# 1-Schematic_SuperCharger_v1.net
KiCad netlist of a schematic drawn in EasyEDA
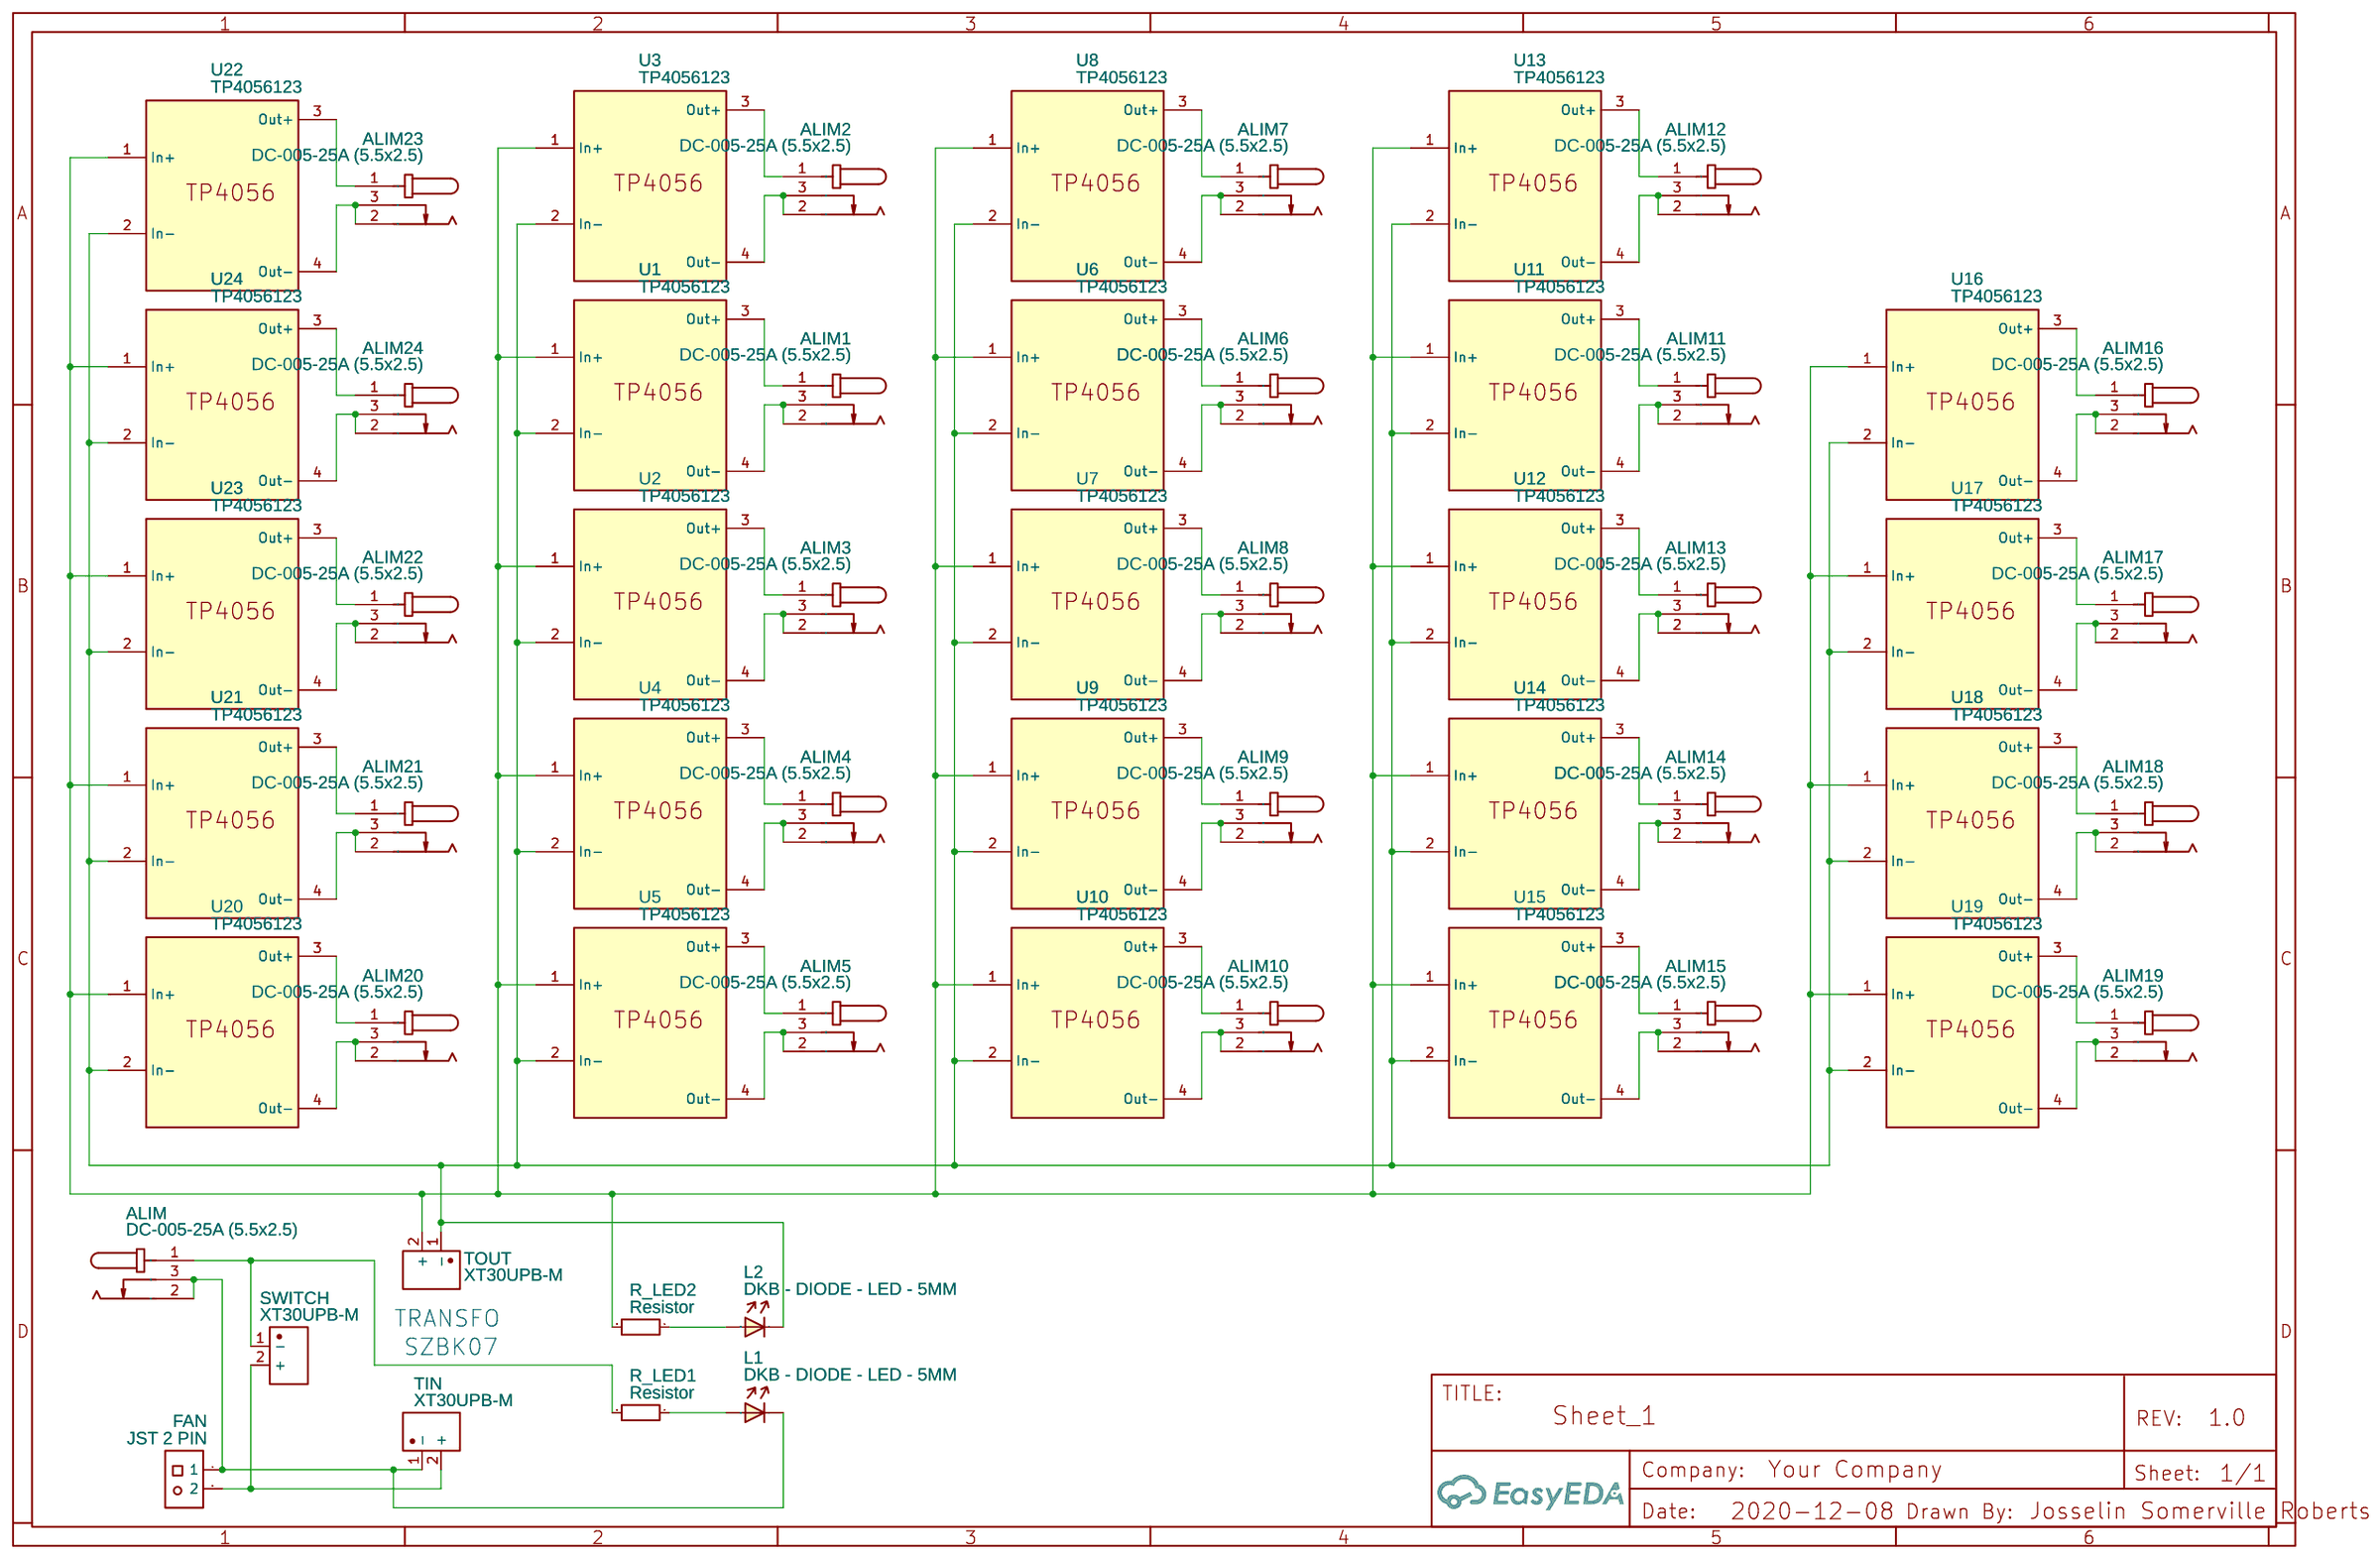
[diagram p0: schematic sheet]

(export (version "E")
  (design (tool "Eeschema 10.0.6"))
  (components
    (comp (ref "ALIM")
      (value "DC-005-25A (5.5x2.5)")
      (fields
        (field (name "BOM_Manufacturer Part") "DC-005-25A")
        (field (name "BOM_Supplier Part") "C136715")
      )
      (libsource (lib "") (part "DC-005-25A (5.5x2.5)_1"))
    )
    (comp (ref "ALIM1")
      (value "DC-005-25A (5.5x2.5)")
      (fields
        (field (name "BOM_Manufacturer Part") "DC-005-25A")
        (field (name "BOM_Supplier Part") "C136715")
      )
      (libsource (lib "") (part "DC-005-25A (5.5x2.5)"))
    )
    (comp (ref "ALIM2")
      (value "DC-005-25A (5.5x2.5)")
      (fields
        (field (name "BOM_Manufacturer Part") "DC-005-25A")
        (field (name "BOM_Supplier Part") "C136715")
      )
      (libsource (lib "") (part "DC-005-25A (5.5x2.5)"))
    )
    (comp (ref "ALIM3")
      (value "DC-005-25A (5.5x2.5)")
      (fields
        (field (name "BOM_Manufacturer Part") "DC-005-25A")
        (field (name "BOM_Supplier Part") "C136715")
      )
      (libsource (lib "") (part "DC-005-25A (5.5x2.5)"))
    )
    (comp (ref "ALIM4")
      (value "DC-005-25A (5.5x2.5)")
      (fields
        (field (name "BOM_Manufacturer Part") "DC-005-25A")
        (field (name "BOM_Supplier Part") "C136715")
      )
      (libsource (lib "") (part "DC-005-25A (5.5x2.5)"))
    )
    (comp (ref "ALIM5")
      (value "DC-005-25A (5.5x2.5)")
      (fields
        (field (name "BOM_Manufacturer Part") "DC-005-25A")
        (field (name "BOM_Supplier Part") "C136715")
      )
      (libsource (lib "") (part "DC-005-25A (5.5x2.5)"))
    )
    (comp (ref "ALIM6")
      (value "DC-005-25A (5.5x2.5)")
      (fields
        (field (name "BOM_Manufacturer Part") "DC-005-25A")
        (field (name "BOM_Supplier Part") "C136715")
      )
      (libsource (lib "") (part "DC-005-25A (5.5x2.5)"))
    )
    (comp (ref "ALIM7")
      (value "DC-005-25A (5.5x2.5)")
      (fields
        (field (name "BOM_Manufacturer Part") "DC-005-25A")
        (field (name "BOM_Supplier Part") "C136715")
      )
      (libsource (lib "") (part "DC-005-25A (5.5x2.5)"))
    )
    (comp (ref "ALIM8")
      (value "DC-005-25A (5.5x2.5)")
      (fields
        (field (name "BOM_Manufacturer Part") "DC-005-25A")
        (field (name "BOM_Supplier Part") "C136715")
      )
      (libsource (lib "") (part "DC-005-25A (5.5x2.5)"))
    )
    (comp (ref "ALIM9")
      (value "DC-005-25A (5.5x2.5)")
      (fields
        (field (name "BOM_Manufacturer Part") "DC-005-25A")
        (field (name "BOM_Supplier Part") "C136715")
      )
      (libsource (lib "") (part "DC-005-25A (5.5x2.5)"))
    )
    (comp (ref "ALIM10")
      (value "DC-005-25A (5.5x2.5)")
      (fields
        (field (name "BOM_Manufacturer Part") "DC-005-25A")
        (field (name "BOM_Supplier Part") "C136715")
      )
      (libsource (lib "") (part "DC-005-25A (5.5x2.5)"))
    )
    (comp (ref "ALIM11")
      (value "DC-005-25A (5.5x2.5)")
      (fields
        (field (name "BOM_Manufacturer Part") "DC-005-25A")
        (field (name "BOM_Supplier Part") "C136715")
      )
      (libsource (lib "") (part "DC-005-25A (5.5x2.5)"))
    )
    (comp (ref "ALIM12")
      (value "DC-005-25A (5.5x2.5)")
      (fields
        (field (name "BOM_Manufacturer Part") "DC-005-25A")
        (field (name "BOM_Supplier Part") "C136715")
      )
      (libsource (lib "") (part "DC-005-25A (5.5x2.5)"))
    )
    (comp (ref "ALIM13")
      (value "DC-005-25A (5.5x2.5)")
      (fields
        (field (name "BOM_Manufacturer Part") "DC-005-25A")
        (field (name "BOM_Supplier Part") "C136715")
      )
      (libsource (lib "") (part "DC-005-25A (5.5x2.5)"))
    )
    (comp (ref "ALIM14")
      (value "DC-005-25A (5.5x2.5)")
      (fields
        (field (name "BOM_Manufacturer Part") "DC-005-25A")
        (field (name "BOM_Supplier Part") "C136715")
      )
      (libsource (lib "") (part "DC-005-25A (5.5x2.5)"))
    )
    (comp (ref "ALIM15")
      (value "DC-005-25A (5.5x2.5)")
      (fields
        (field (name "BOM_Manufacturer Part") "DC-005-25A")
        (field (name "BOM_Supplier Part") "C136715")
      )
      (libsource (lib "") (part "DC-005-25A (5.5x2.5)"))
    )
    (comp (ref "ALIM16")
      (value "DC-005-25A (5.5x2.5)")
      (fields
        (field (name "BOM_Manufacturer Part") "DC-005-25A")
        (field (name "BOM_Supplier Part") "C136715")
      )
      (libsource (lib "") (part "DC-005-25A (5.5x2.5)"))
    )
    (comp (ref "ALIM17")
      (value "DC-005-25A (5.5x2.5)")
      (fields
        (field (name "BOM_Manufacturer Part") "DC-005-25A")
        (field (name "BOM_Supplier Part") "C136715")
      )
      (libsource (lib "") (part "DC-005-25A (5.5x2.5)"))
    )
    (comp (ref "ALIM18")
      (value "DC-005-25A (5.5x2.5)")
      (fields
        (field (name "BOM_Manufacturer Part") "DC-005-25A")
        (field (name "BOM_Supplier Part") "C136715")
      )
      (libsource (lib "") (part "DC-005-25A (5.5x2.5)"))
    )
    (comp (ref "ALIM19")
      (value "DC-005-25A (5.5x2.5)")
      (fields
        (field (name "BOM_Manufacturer Part") "DC-005-25A")
        (field (name "BOM_Supplier Part") "C136715")
      )
      (libsource (lib "") (part "DC-005-25A (5.5x2.5)"))
    )
    (comp (ref "ALIM20")
      (value "DC-005-25A (5.5x2.5)")
      (fields
        (field (name "BOM_Manufacturer Part") "DC-005-25A")
        (field (name "BOM_Supplier Part") "C136715")
      )
      (libsource (lib "") (part "DC-005-25A (5.5x2.5)"))
    )
    (comp (ref "ALIM21")
      (value "DC-005-25A (5.5x2.5)")
      (fields
        (field (name "BOM_Manufacturer Part") "DC-005-25A")
        (field (name "BOM_Supplier Part") "C136715")
      )
      (libsource (lib "") (part "DC-005-25A (5.5x2.5)"))
    )
    (comp (ref "ALIM22")
      (value "DC-005-25A (5.5x2.5)")
      (fields
        (field (name "BOM_Manufacturer Part") "DC-005-25A")
        (field (name "BOM_Supplier Part") "C136715")
      )
      (libsource (lib "") (part "DC-005-25A (5.5x2.5)"))
    )
    (comp (ref "ALIM23")
      (value "DC-005-25A (5.5x2.5)")
      (fields
        (field (name "BOM_Manufacturer Part") "DC-005-25A")
        (field (name "BOM_Supplier Part") "C136715")
      )
      (libsource (lib "") (part "DC-005-25A (5.5x2.5)"))
    )
    (comp (ref "ALIM24")
      (value "DC-005-25A (5.5x2.5)")
      (fields
        (field (name "BOM_Manufacturer Part") "DC-005-25A")
        (field (name "BOM_Supplier Part") "C136715")
      )
      (libsource (lib "") (part "DC-005-25A (5.5x2.5)"))
    )
    (comp (ref "FAN")
      (value "JST 2 PIN")
      (fields (field (name "BOM_Manufacturer Part") "JST_XH CONNECTOR"))
      (libsource (lib "") (part "JST 2 PIN"))
    )
    (comp (ref "L1")
      (value "DKB - DIODE - LED - 5MM")
      (fields (field (name "BOM_Manufacturer Part") "5mm LED"))
      (libsource (lib "") (part "DKB - DIODE - LED - 5MM"))
    )
    (comp (ref "L2")
      (value "DKB - DIODE - LED - 5MM")
      (fields (field (name "BOM_Manufacturer Part") "5mm LED"))
      (libsource (lib "") (part "DKB - DIODE - LED - 5MM"))
    )
    (comp (ref "R_LED1") (value "Resistor") (libsource (lib "") (part "Resistor")))
    (comp (ref "R_LED2") (value "Resistor") (libsource (lib "") (part "Resistor")))
    (comp (ref "SWITCH")
      (value "XT30UPB-M")
      (fields (field (name "BOM_Supplier Part") "C428721"))
      (libsource (lib "") (part "XT30UPB-M"))
    )
    (comp (ref "TIN")
      (value "XT30UPB-M")
      (fields (field (name "BOM_Supplier Part") "C428721"))
      (libsource (lib "") (part "XT30UPB-M_1"))
    )
    (comp (ref "TOUT")
      (value "XT30UPB-M")
      (fields (field (name "BOM_Supplier Part") "C428721"))
      (libsource (lib "") (part "XT30UPB-M_2"))
    )
    (comp (ref "U1") (value "TP4056123") (libsource (lib "") (part "TP4056123")))
    (comp (ref "U2") (value "TP4056123") (libsource (lib "") (part "TP4056123")))
    (comp (ref "U3") (value "TP4056123") (libsource (lib "") (part "TP4056123")))
    (comp (ref "U4") (value "TP4056123") (libsource (lib "") (part "TP4056123")))
    (comp (ref "U5") (value "TP4056123") (libsource (lib "") (part "TP4056123")))
    (comp (ref "U6") (value "TP4056123") (libsource (lib "") (part "TP4056123")))
    (comp (ref "U7") (value "TP4056123") (libsource (lib "") (part "TP4056123")))
    (comp (ref "U8") (value "TP4056123") (libsource (lib "") (part "TP4056123")))
    (comp (ref "U9") (value "TP4056123") (libsource (lib "") (part "TP4056123")))
    (comp (ref "U10") (value "TP4056123") (libsource (lib "") (part "TP4056123")))
    (comp (ref "U11") (value "TP4056123") (libsource (lib "") (part "TP4056123")))
    (comp (ref "U12") (value "TP4056123") (libsource (lib "") (part "TP4056123")))
    (comp (ref "U13") (value "TP4056123") (libsource (lib "") (part "TP4056123")))
    (comp (ref "U14") (value "TP4056123") (libsource (lib "") (part "TP4056123")))
    (comp (ref "U15") (value "TP4056123") (libsource (lib "") (part "TP4056123")))
    (comp (ref "U16") (value "TP4056123") (libsource (lib "") (part "TP4056123")))
    (comp (ref "U17") (value "TP4056123") (libsource (lib "") (part "TP4056123")))
    (comp (ref "U18") (value "TP4056123") (libsource (lib "") (part "TP4056123")))
    (comp (ref "U19") (value "TP4056123") (libsource (lib "") (part "TP4056123")))
    (comp (ref "U20") (value "TP4056123") (libsource (lib "") (part "TP4056123")))
    (comp (ref "U21") (value "TP4056123") (libsource (lib "") (part "TP4056123")))
    (comp (ref "U22") (value "TP4056123") (libsource (lib "") (part "TP4056123")))
    (comp (ref "U23") (value "TP4056123") (libsource (lib "") (part "TP4056123")))
    (comp (ref "U24") (value "TP4056123") (libsource (lib "") (part "TP4056123")))
  )
  (nets
    (net (code "1") (name "Net-(L1-Pad1)") (class "Default")
      (node (ref "L1") (pin "1") (pinfunction "1_1") (pintype "unspecified"))
      (node (ref "R_LED1") (pin "1") (pintype "unspecified"))
    )
    (net (code "2") (name "Net-(L2-Pad1)") (class "Default")
      (node (ref "L2") (pin "1") (pinfunction "1_1") (pintype "unspecified"))
      (node (ref "R_LED2") (pin "1") (pintype "unspecified"))
    )
    (net (code "3") (name "Net-(SWITCH-+)") (class "Default")
      (node (ref "FAN") (pin "2") (pinfunction "2_2") (pintype "unspecified"))
      (node (ref "SWITCH") (pin "2") (pinfunction "+_2") (pintype "unspecified"))
      (node (ref "TIN") (pin "2") (pinfunction "+_2") (pintype "unspecified"))
    )
    (net (code "4") (name "Net-(SWITCH--)") (class "Default")
      (node (ref "ALIM") (pin "1") (pinfunction "1_1") (pintype "unspecified"))
      (node (ref "R_LED1") (pin "2") (pintype "unspecified"))
      (node (ref "SWITCH") (pin "1") (pinfunction "-_1") (pintype "unspecified"))
    )
    (net (code "5") (name "Net-(TIN--)") (class "Default")
      (node (ref "ALIM") (pin "2") (pinfunction "2_2") (pintype "unspecified"))
      (node (ref "ALIM") (pin "3") (pinfunction "3_3") (pintype "unspecified"))
      (node (ref "FAN") (pin "1") (pinfunction "1_1") (pintype "unspecified"))
      (node (ref "L1") (pin "2") (pinfunction "2_2") (pintype "unspecified"))
      (node (ref "TIN") (pin "1") (pinfunction "-_1") (pintype "unspecified"))
    )
    (net (code "6") (name "Net-(TOUT-+)") (class "Default")
      (node (ref "R_LED2") (pin "2") (pintype "unspecified"))
      (node (ref "TOUT") (pin "2") (pinfunction "+_2") (pintype "unspecified"))
      (node (ref "U1") (pin "1") (pinfunction "In+_1") (pintype "unspecified"))
      (node (ref "U10") (pin "1") (pinfunction "In+_1") (pintype "unspecified"))
      (node (ref "U11") (pin "1") (pinfunction "In+_1") (pintype "unspecified"))
      (node (ref "U12") (pin "1") (pinfunction "In+_1") (pintype "unspecified"))
      (node (ref "U13") (pin "1") (pinfunction "In+_1") (pintype "unspecified"))
      (node (ref "U14") (pin "1") (pinfunction "In+_1") (pintype "unspecified"))
      (node (ref "U15") (pin "1") (pinfunction "In+_1") (pintype "unspecified"))
      (node (ref "U16") (pin "1") (pinfunction "In+_1") (pintype "unspecified"))
      (node (ref "U17") (pin "1") (pinfunction "In+_1") (pintype "unspecified"))
      (node (ref "U18") (pin "1") (pinfunction "In+_1") (pintype "unspecified"))
      (node (ref "U19") (pin "1") (pinfunction "In+_1") (pintype "unspecified"))
      (node (ref "U2") (pin "1") (pinfunction "In+_1") (pintype "unspecified"))
      (node (ref "U20") (pin "1") (pinfunction "In+_1") (pintype "unspecified"))
      (node (ref "U21") (pin "1") (pinfunction "In+_1") (pintype "unspecified"))
      (node (ref "U22") (pin "1") (pinfunction "In+_1") (pintype "unspecified"))
      (node (ref "U23") (pin "1") (pinfunction "In+_1") (pintype "unspecified"))
      (node (ref "U24") (pin "1") (pinfunction "In+_1") (pintype "unspecified"))
      (node (ref "U3") (pin "1") (pinfunction "In+_1") (pintype "unspecified"))
      (node (ref "U4") (pin "1") (pinfunction "In+_1") (pintype "unspecified"))
      (node (ref "U5") (pin "1") (pinfunction "In+_1") (pintype "unspecified"))
      (node (ref "U6") (pin "1") (pinfunction "In+_1") (pintype "unspecified"))
      (node (ref "U7") (pin "1") (pinfunction "In+_1") (pintype "unspecified"))
      (node (ref "U8") (pin "1") (pinfunction "In+_1") (pintype "unspecified"))
      (node (ref "U9") (pin "1") (pinfunction "In+_1") (pintype "unspecified"))
    )
    (net (code "7") (name "Net-(TOUT--)") (class "Default")
      (node (ref "L2") (pin "2") (pinfunction "2_2") (pintype "unspecified"))
      (node (ref "TOUT") (pin "1") (pinfunction "-_1") (pintype "unspecified"))
      (node (ref "U1") (pin "2") (pinfunction "In-_2") (pintype "unspecified"))
      (node (ref "U10") (pin "2") (pinfunction "In-_2") (pintype "unspecified"))
      (node (ref "U11") (pin "2") (pinfunction "In-_2") (pintype "unspecified"))
      (node (ref "U12") (pin "2") (pinfunction "In-_2") (pintype "unspecified"))
      (node (ref "U13") (pin "2") (pinfunction "In-_2") (pintype "unspecified"))
      (node (ref "U14") (pin "2") (pinfunction "In-_2") (pintype "unspecified"))
      (node (ref "U15") (pin "2") (pinfunction "In-_2") (pintype "unspecified"))
      (node (ref "U16") (pin "2") (pinfunction "In-_2") (pintype "unspecified"))
      (node (ref "U17") (pin "2") (pinfunction "In-_2") (pintype "unspecified"))
      (node (ref "U18") (pin "2") (pinfunction "In-_2") (pintype "unspecified"))
      (node (ref "U19") (pin "2") (pinfunction "In-_2") (pintype "unspecified"))
      (node (ref "U2") (pin "2") (pinfunction "In-_2") (pintype "unspecified"))
      (node (ref "U20") (pin "2") (pinfunction "In-_2") (pintype "unspecified"))
      (node (ref "U21") (pin "2") (pinfunction "In-_2") (pintype "unspecified"))
      (node (ref "U22") (pin "2") (pinfunction "In-_2") (pintype "unspecified"))
      (node (ref "U23") (pin "2") (pinfunction "In-_2") (pintype "unspecified"))
      (node (ref "U24") (pin "2") (pinfunction "In-_2") (pintype "unspecified"))
      (node (ref "U3") (pin "2") (pinfunction "In-_2") (pintype "unspecified"))
      (node (ref "U4") (pin "2") (pinfunction "In-_2") (pintype "unspecified"))
      (node (ref "U5") (pin "2") (pinfunction "In-_2") (pintype "unspecified"))
      (node (ref "U6") (pin "2") (pinfunction "In-_2") (pintype "unspecified"))
      (node (ref "U7") (pin "2") (pinfunction "In-_2") (pintype "unspecified"))
      (node (ref "U8") (pin "2") (pinfunction "In-_2") (pintype "unspecified"))
      (node (ref "U9") (pin "2") (pinfunction "In-_2") (pintype "unspecified"))
    )
    (net (code "8") (name "Net-(U1-Out+)") (class "Default")
      (node (ref "ALIM1") (pin "1") (pinfunction "1_1") (pintype "unspecified"))
      (node (ref "U1") (pin "3") (pinfunction "Out+_3") (pintype "unspecified"))
    )
    (net (code "9") (name "Net-(U1-Out-)") (class "Default")
      (node (ref "ALIM1") (pin "2") (pinfunction "2_2") (pintype "unspecified"))
      (node (ref "ALIM1") (pin "3") (pinfunction "3_3") (pintype "unspecified"))
      (node (ref "U1") (pin "4") (pinfunction "Out-_4") (pintype "unspecified"))
    )
    (net (code "10") (name "Net-(U2-Out+)") (class "Default")
      (node (ref "ALIM3") (pin "1") (pinfunction "1_1") (pintype "unspecified"))
      (node (ref "U2") (pin "3") (pinfunction "Out+_3") (pintype "unspecified"))
    )
    (net (code "11") (name "Net-(U2-Out-)") (class "Default")
      (node (ref "ALIM3") (pin "2") (pinfunction "2_2") (pintype "unspecified"))
      (node (ref "ALIM3") (pin "3") (pinfunction "3_3") (pintype "unspecified"))
      (node (ref "U2") (pin "4") (pinfunction "Out-_4") (pintype "unspecified"))
    )
    (net (code "12") (name "Net-(U3-Out+)") (class "Default")
      (node (ref "ALIM2") (pin "1") (pinfunction "1_1") (pintype "unspecified"))
      (node (ref "U3") (pin "3") (pinfunction "Out+_3") (pintype "unspecified"))
    )
    (net (code "13") (name "Net-(U3-Out-)") (class "Default")
      (node (ref "ALIM2") (pin "2") (pinfunction "2_2") (pintype "unspecified"))
      (node (ref "ALIM2") (pin "3") (pinfunction "3_3") (pintype "unspecified"))
      (node (ref "U3") (pin "4") (pinfunction "Out-_4") (pintype "unspecified"))
    )
    (net (code "14") (name "Net-(U4-Out+)") (class "Default")
      (node (ref "ALIM4") (pin "1") (pinfunction "1_1") (pintype "unspecified"))
      (node (ref "U4") (pin "3") (pinfunction "Out+_3") (pintype "unspecified"))
    )
    (net (code "15") (name "Net-(U4-Out-)") (class "Default")
      (node (ref "ALIM4") (pin "2") (pinfunction "2_2") (pintype "unspecified"))
      (node (ref "ALIM4") (pin "3") (pinfunction "3_3") (pintype "unspecified"))
      (node (ref "U4") (pin "4") (pinfunction "Out-_4") (pintype "unspecified"))
    )
    (net (code "16") (name "Net-(U5-Out+)") (class "Default")
      (node (ref "ALIM5") (pin "1") (pinfunction "1_1") (pintype "unspecified"))
      (node (ref "U5") (pin "3") (pinfunction "Out+_3") (pintype "unspecified"))
    )
    (net (code "17") (name "Net-(U5-Out-)") (class "Default")
      (node (ref "ALIM5") (pin "2") (pinfunction "2_2") (pintype "unspecified"))
      (node (ref "ALIM5") (pin "3") (pinfunction "3_3") (pintype "unspecified"))
      (node (ref "U5") (pin "4") (pinfunction "Out-_4") (pintype "unspecified"))
    )
    (net (code "18") (name "Net-(U6-Out+)") (class "Default")
      (node (ref "ALIM6") (pin "1") (pinfunction "1_1") (pintype "unspecified"))
      (node (ref "U6") (pin "3") (pinfunction "Out+_3") (pintype "unspecified"))
    )
    (net (code "19") (name "Net-(U6-Out-)") (class "Default")
      (node (ref "ALIM6") (pin "2") (pinfunction "2_2") (pintype "unspecified"))
      (node (ref "ALIM6") (pin "3") (pinfunction "3_3") (pintype "unspecified"))
      (node (ref "U6") (pin "4") (pinfunction "Out-_4") (pintype "unspecified"))
    )
    (net (code "20") (name "Net-(U7-Out+)") (class "Default")
      (node (ref "ALIM8") (pin "1") (pinfunction "1_1") (pintype "unspecified"))
      (node (ref "U7") (pin "3") (pinfunction "Out+_3") (pintype "unspecified"))
    )
    (net (code "21") (name "Net-(U7-Out-)") (class "Default")
      (node (ref "ALIM8") (pin "2") (pinfunction "2_2") (pintype "unspecified"))
      (node (ref "ALIM8") (pin "3") (pinfunction "3_3") (pintype "unspecified"))
      (node (ref "U7") (pin "4") (pinfunction "Out-_4") (pintype "unspecified"))
    )
    (net (code "22") (name "Net-(U8-Out+)") (class "Default")
      (node (ref "ALIM7") (pin "1") (pinfunction "1_1") (pintype "unspecified"))
      (node (ref "U8") (pin "3") (pinfunction "Out+_3") (pintype "unspecified"))
    )
    (net (code "23") (name "Net-(U8-Out-)") (class "Default")
      (node (ref "ALIM7") (pin "2") (pinfunction "2_2") (pintype "unspecified"))
      (node (ref "ALIM7") (pin "3") (pinfunction "3_3") (pintype "unspecified"))
      (node (ref "U8") (pin "4") (pinfunction "Out-_4") (pintype "unspecified"))
    )
    (net (code "24") (name "Net-(U9-Out+)") (class "Default")
      (node (ref "ALIM9") (pin "1") (pinfunction "1_1") (pintype "unspecified"))
      (node (ref "U9") (pin "3") (pinfunction "Out+_3") (pintype "unspecified"))
    )
    (net (code "25") (name "Net-(U9-Out-)") (class "Default")
      (node (ref "ALIM9") (pin "2") (pinfunction "2_2") (pintype "unspecified"))
      (node (ref "ALIM9") (pin "3") (pinfunction "3_3") (pintype "unspecified"))
      (node (ref "U9") (pin "4") (pinfunction "Out-_4") (pintype "unspecified"))
    )
    (net (code "26") (name "Net-(U10-Out+)") (class "Default")
      (node (ref "ALIM10") (pin "1") (pinfunction "1_1") (pintype "unspecified"))
      (node (ref "U10") (pin "3") (pinfunction "Out+_3") (pintype "unspecified"))
    )
    (net (code "27") (name "Net-(U10-Out-)") (class "Default")
      (node (ref "ALIM10") (pin "2") (pinfunction "2_2") (pintype "unspecified"))
      (node (ref "ALIM10") (pin "3") (pinfunction "3_3") (pintype "unspecified"))
      (node (ref "U10") (pin "4") (pinfunction "Out-_4") (pintype "unspecified"))
    )
    (net (code "28") (name "Net-(U11-Out+)") (class "Default")
      (node (ref "ALIM11") (pin "1") (pinfunction "1_1") (pintype "unspecified"))
      (node (ref "U11") (pin "3") (pinfunction "Out+_3") (pintype "unspecified"))
    )
    (net (code "29") (name "Net-(U11-Out-)") (class "Default")
      (node (ref "ALIM11") (pin "2") (pinfunction "2_2") (pintype "unspecified"))
      (node (ref "ALIM11") (pin "3") (pinfunction "3_3") (pintype "unspecified"))
      (node (ref "U11") (pin "4") (pinfunction "Out-_4") (pintype "unspecified"))
    )
    (net (code "30") (name "Net-(U12-Out+)") (class "Default")
      (node (ref "ALIM13") (pin "1") (pinfunction "1_1") (pintype "unspecified"))
      (node (ref "U12") (pin "3") (pinfunction "Out+_3") (pintype "unspecified"))
    )
    (net (code "31") (name "Net-(U12-Out-)") (class "Default")
      (node (ref "ALIM13") (pin "2") (pinfunction "2_2") (pintype "unspecified"))
      (node (ref "ALIM13") (pin "3") (pinfunction "3_3") (pintype "unspecified"))
      (node (ref "U12") (pin "4") (pinfunction "Out-_4") (pintype "unspecified"))
    )
    (net (code "32") (name "Net-(U13-Out+)") (class "Default")
      (node (ref "ALIM12") (pin "1") (pinfunction "1_1") (pintype "unspecified"))
      (node (ref "U13") (pin "3") (pinfunction "Out+_3") (pintype "unspecified"))
    )
    (net (code "33") (name "Net-(U13-Out-)") (class "Default")
      (node (ref "ALIM12") (pin "2") (pinfunction "2_2") (pintype "unspecified"))
      (node (ref "ALIM12") (pin "3") (pinfunction "3_3") (pintype "unspecified"))
      (node (ref "U13") (pin "4") (pinfunction "Out-_4") (pintype "unspecified"))
    )
    (net (code "34") (name "Net-(U14-Out+)") (class "Default")
      (node (ref "ALIM14") (pin "1") (pinfunction "1_1") (pintype "unspecified"))
      (node (ref "U14") (pin "3") (pinfunction "Out+_3") (pintype "unspecified"))
    )
    (net (code "35") (name "Net-(U14-Out-)") (class "Default")
      (node (ref "ALIM14") (pin "2") (pinfunction "2_2") (pintype "unspecified"))
      (node (ref "ALIM14") (pin "3") (pinfunction "3_3") (pintype "unspecified"))
      (node (ref "U14") (pin "4") (pinfunction "Out-_4") (pintype "unspecified"))
    )
    (net (code "36") (name "Net-(U15-Out+)") (class "Default")
      (node (ref "ALIM15") (pin "1") (pinfunction "1_1") (pintype "unspecified"))
      (node (ref "U15") (pin "3") (pinfunction "Out+_3") (pintype "unspecified"))
    )
    (net (code "37") (name "Net-(U15-Out-)") (class "Default")
      (node (ref "ALIM15") (pin "2") (pinfunction "2_2") (pintype "unspecified"))
      (node (ref "ALIM15") (pin "3") (pinfunction "3_3") (pintype "unspecified"))
      (node (ref "U15") (pin "4") (pinfunction "Out-_4") (pintype "unspecified"))
    )
    (net (code "38") (name "Net-(U16-Out+)") (class "Default")
      (node (ref "ALIM16") (pin "1") (pinfunction "1_1") (pintype "unspecified"))
      (node (ref "U16") (pin "3") (pinfunction "Out+_3") (pintype "unspecified"))
    )
    (net (code "39") (name "Net-(U16-Out-)") (class "Default")
      (node (ref "ALIM16") (pin "2") (pinfunction "2_2") (pintype "unspecified"))
      (node (ref "ALIM16") (pin "3") (pinfunction "3_3") (pintype "unspecified"))
      (node (ref "U16") (pin "4") (pinfunction "Out-_4") (pintype "unspecified"))
    )
    (net (code "40") (name "Net-(U17-Out+)") (class "Default")
      (node (ref "ALIM17") (pin "1") (pinfunction "1_1") (pintype "unspecified"))
      (node (ref "U17") (pin "3") (pinfunction "Out+_3") (pintype "unspecified"))
    )
    (net (code "41") (name "Net-(U17-Out-)") (class "Default")
      (node (ref "ALIM17") (pin "2") (pinfunction "2_2") (pintype "unspecified"))
      (node (ref "ALIM17") (pin "3") (pinfunction "3_3") (pintype "unspecified"))
      (node (ref "U17") (pin "4") (pinfunction "Out-_4") (pintype "unspecified"))
    )
    (net (code "42") (name "Net-(U18-Out+)") (class "Default")
      (node (ref "ALIM18") (pin "1") (pinfunction "1_1") (pintype "unspecified"))
      (node (ref "U18") (pin "3") (pinfunction "Out+_3") (pintype "unspecified"))
    )
    (net (code "43") (name "Net-(U18-Out-)") (class "Default")
      (node (ref "ALIM18") (pin "2") (pinfunction "2_2") (pintype "unspecified"))
      (node (ref "ALIM18") (pin "3") (pinfunction "3_3") (pintype "unspecified"))
      (node (ref "U18") (pin "4") (pinfunction "Out-_4") (pintype "unspecified"))
    )
    (net (code "44") (name "Net-(U19-Out+)") (class "Default")
      (node (ref "ALIM19") (pin "1") (pinfunction "1_1") (pintype "unspecified"))
      (node (ref "U19") (pin "3") (pinfunction "Out+_3") (pintype "unspecified"))
    )
    (net (code "45") (name "Net-(U19-Out-)") (class "Default")
      (node (ref "ALIM19") (pin "2") (pinfunction "2_2") (pintype "unspecified"))
      (node (ref "ALIM19") (pin "3") (pinfunction "3_3") (pintype "unspecified"))
      (node (ref "U19") (pin "4") (pinfunction "Out-_4") (pintype "unspecified"))
    )
    (net (code "46") (name "Net-(U20-Out+)") (class "Default")
      (node (ref "ALIM20") (pin "1") (pinfunction "1_1") (pintype "unspecified"))
      (node (ref "U20") (pin "3") (pinfunction "Out+_3") (pintype "unspecified"))
    )
    (net (code "47") (name "Net-(U20-Out-)") (class "Default")
      (node (ref "ALIM20") (pin "2") (pinfunction "2_2") (pintype "unspecified"))
      (node (ref "ALIM20") (pin "3") (pinfunction "3_3") (pintype "unspecified"))
      (node (ref "U20") (pin "4") (pinfunction "Out-_4") (pintype "unspecified"))
    )
    (net (code "48") (name "Net-(U21-Out+)") (class "Default")
      (node (ref "ALIM21") (pin "1") (pinfunction "1_1") (pintype "unspecified"))
      (node (ref "U21") (pin "3") (pinfunction "Out+_3") (pintype "unspecified"))
    )
    (net (code "49") (name "Net-(U21-Out-)") (class "Default")
      (node (ref "ALIM21") (pin "2") (pinfunction "2_2") (pintype "unspecified"))
      (node (ref "ALIM21") (pin "3") (pinfunction "3_3") (pintype "unspecified"))
      (node (ref "U21") (pin "4") (pinfunction "Out-_4") (pintype "unspecified"))
    )
    (net (code "50") (name "Net-(U22-Out+)") (class "Default")
      (node (ref "ALIM23") (pin "1") (pinfunction "1_1") (pintype "unspecified"))
      (node (ref "U22") (pin "3") (pinfunction "Out+_3") (pintype "unspecified"))
    )
    (net (code "51") (name "Net-(U22-Out-)") (class "Default")
      (node (ref "ALIM23") (pin "2") (pinfunction "2_2") (pintype "unspecified"))
      (node (ref "ALIM23") (pin "3") (pinfunction "3_3") (pintype "unspecified"))
      (node (ref "U22") (pin "4") (pinfunction "Out-_4") (pintype "unspecified"))
    )
    (net (code "52") (name "Net-(U23-Out+)") (class "Default")
      (node (ref "ALIM22") (pin "1") (pinfunction "1_1") (pintype "unspecified"))
      (node (ref "U23") (pin "3") (pinfunction "Out+_3") (pintype "unspecified"))
    )
    (net (code "53") (name "Net-(U23-Out-)") (class "Default")
      (node (ref "ALIM22") (pin "2") (pinfunction "2_2") (pintype "unspecified"))
      (node (ref "ALIM22") (pin "3") (pinfunction "3_3") (pintype "unspecified"))
      (node (ref "U23") (pin "4") (pinfunction "Out-_4") (pintype "unspecified"))
    )
    (net (code "54") (name "Net-(U24-Out+)") (class "Default")
      (node (ref "ALIM24") (pin "1") (pinfunction "1_1") (pintype "unspecified"))
      (node (ref "U24") (pin "3") (pinfunction "Out+_3") (pintype "unspecified"))
    )
    (net (code "55") (name "Net-(U24-Out-)") (class "Default")
      (node (ref "ALIM24") (pin "2") (pinfunction "2_2") (pintype "unspecified"))
      (node (ref "ALIM24") (pin "3") (pinfunction "3_3") (pintype "unspecified"))
      (node (ref "U24") (pin "4") (pinfunction "Out-_4") (pintype "unspecified"))
    )
  )
)
